# SolBout.net
KiCad netlist of a schematic drawn in Altium Designer
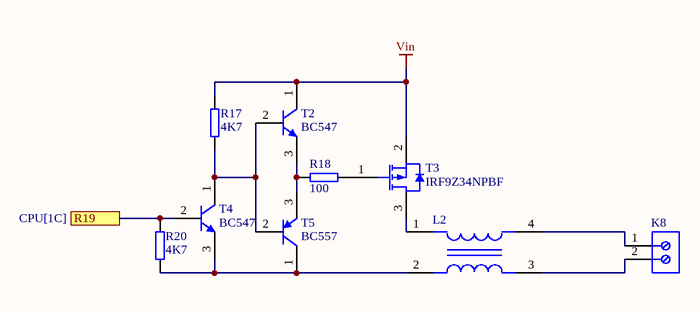
[diagram p0: SolBout.SchDoc]

(export (version "E")
  (design (tool "Eeschema 10.0.6"))
  (components
    (comp (ref "K8")
      (value "~")
      (footprint "TECO-282836-2_V")
      (description "Female Header, Pitch 5 mm, 1 x 2 Position, Height 10 mm, Tail Length 3.5 mm, Rohs, Bulk")
      (fields (field (name "VOLTAGE") "300V") (field (name "MANUFACTURER") "TE Connectivity"))
      (libsource (lib "Soldeerstation_Final") (part "CMP-1684-00017-1"))
    )
    (comp (ref "L2")
      (value "~")
      (footprint "2545")
      (libsource (lib "Soldeerstation_Final") (part "Common_Mode_Choke"))
    )
    (comp (ref "R17")
      (value "4K7")
      (footprint "0805_M")
      (fields (field (name "MANUFACTURER") "Vishay Dale") (field (name "PART NUMBER") "CRCW08050000Z0EA"))
      (libsource (lib "Soldeerstation_Final") (part "Resistor"))
    )
    (comp (ref "R18")
      (value "100")
      (footprint "0805_M")
      (fields (field (name "MANUFACTURER") "Vishay Dale") (field (name "PART NUMBER") "CRCW08050000Z0EA"))
      (libsource (lib "Soldeerstation_Final") (part "Resistor"))
    )
    (comp (ref "R20")
      (value "4K7")
      (footprint "0805_M")
      (fields (field (name "MANUFACTURER") "Vishay Dale") (field (name "PART NUMBER") "CRCW08050000Z0EA"))
      (libsource (lib "Soldeerstation_Final") (part "Resistor"))
    )
    (comp (ref "T2")
      (value "BC547")
      (footprint "SOT_23")
      (fields (field (name "MANUFACTURER") "On Semiconductor") (field (name "PARTNUMBER") "BC547C"))
      (libsource (lib "Soldeerstation_Final") (part "Transistor_NPN"))
    )
    (comp (ref "T3")
      (value "IRF9Z34NPBF")
      (footprint "TO_252")
      (fields (field (name "MANUFACTURER") "Fairchild Semiconductor"))
      (libsource (lib "Soldeerstation_Final") (part "MOSFET_P"))
    )
    (comp (ref "T4")
      (value "BC547")
      (footprint "SOT_23")
      (fields (field (name "MANUFACTURER") "On Semiconductor") (field (name "PARTNUMBER") "BC547C"))
      (libsource (lib "Soldeerstation_Final") (part "Transistor_NPN"))
    )
    (comp (ref "T5")
      (value "BC557")
      (footprint "SOT_23")
      (fields (field (name "MANUFACTURER") "On Semiconductor") (field (name "PARTNUMBER") "BC557C"))
      (libsource (lib "Soldeerstation_Final") (part "Transistor_PNP"))
    )
  )
  (nets
    (net (code "1") (name "/R19") (class "Default")
      (node (ref "R20") (pin "2") (pinfunction "2_2") (pintype "passive"))
      (node (ref "T4") (pin "2") (pinfunction "B_2") (pintype "passive"))
    )
    (net (code "2") (name "Net-(K8-Pad1)") (class "Default")
      (node (ref "K8") (pin "1") (pinfunction "1_1") (pintype "passive"))
      (node (ref "L2") (pin "4") (pinfunction "4_4") (pintype "passive"))
    )
    (net (code "3") (name "Net-(K8-Pad2)") (class "Default")
      (node (ref "K8") (pin "2") (pinfunction "2_2") (pintype "passive"))
      (node (ref "L2") (pin "3") (pinfunction "3_3") (pintype "passive"))
    )
    (net (code "4") (name "Net-(T2-B)") (class "Default")
      (node (ref "R17") (pin "1") (pinfunction "1_1") (pintype "passive"))
      (node (ref "T2") (pin "2") (pinfunction "B_2") (pintype "passive"))
      (node (ref "T4") (pin "1") (pinfunction "C_1") (pintype "passive"))
      (node (ref "T5") (pin "2") (pinfunction "B_2") (pintype "passive"))
    )
    (net (code "5") (name "Net-(T2-E)") (class "Default")
      (node (ref "R18") (pin "1") (pinfunction "1_1") (pintype "passive"))
      (node (ref "T2") (pin "3") (pinfunction "E_3") (pintype "passive"))
      (node (ref "T5") (pin "3") (pinfunction "E_3") (pintype "passive"))
    )
    (net (code "6") (name "Net-(T3-DRAIN)") (class "Default")
      (node (ref "L2") (pin "1") (pinfunction "1_1") (pintype "passive"))
      (node (ref "T3") (pin "3") (pinfunction "DRAIN_3") (pintype "passive"))
    )
    (net (code "7") (name "Net-(T3-GATE)") (class "Default")
      (node (ref "R18") (pin "2") (pinfunction "2_2") (pintype "passive"))
      (node (ref "T3") (pin "1") (pinfunction "GATE_1") (pintype "passive"))
    )
    (net (code "8") (name "Net-(T4-E)") (class "Default")
      (node (ref "L2") (pin "2") (pinfunction "2_2") (pintype "passive"))
      (node (ref "R20") (pin "1") (pinfunction "1_1") (pintype "passive"))
      (node (ref "T4") (pin "3") (pinfunction "E_3") (pintype "passive"))
      (node (ref "T5") (pin "1") (pinfunction "C_1") (pintype "passive"))
    )
    (net (code "9") (name "Vin") (class "Default")
      (node (ref "R17") (pin "2") (pinfunction "2_2") (pintype "passive"))
      (node (ref "T2") (pin "1") (pinfunction "C_1") (pintype "passive"))
      (node (ref "T3") (pin "2") (pinfunction "SOURCE_2") (pintype "passive"))
    )
  )
)
